# RK-POWER-SUPPLY.net
KiCad netlist of a schematic drawn in Altium Designer
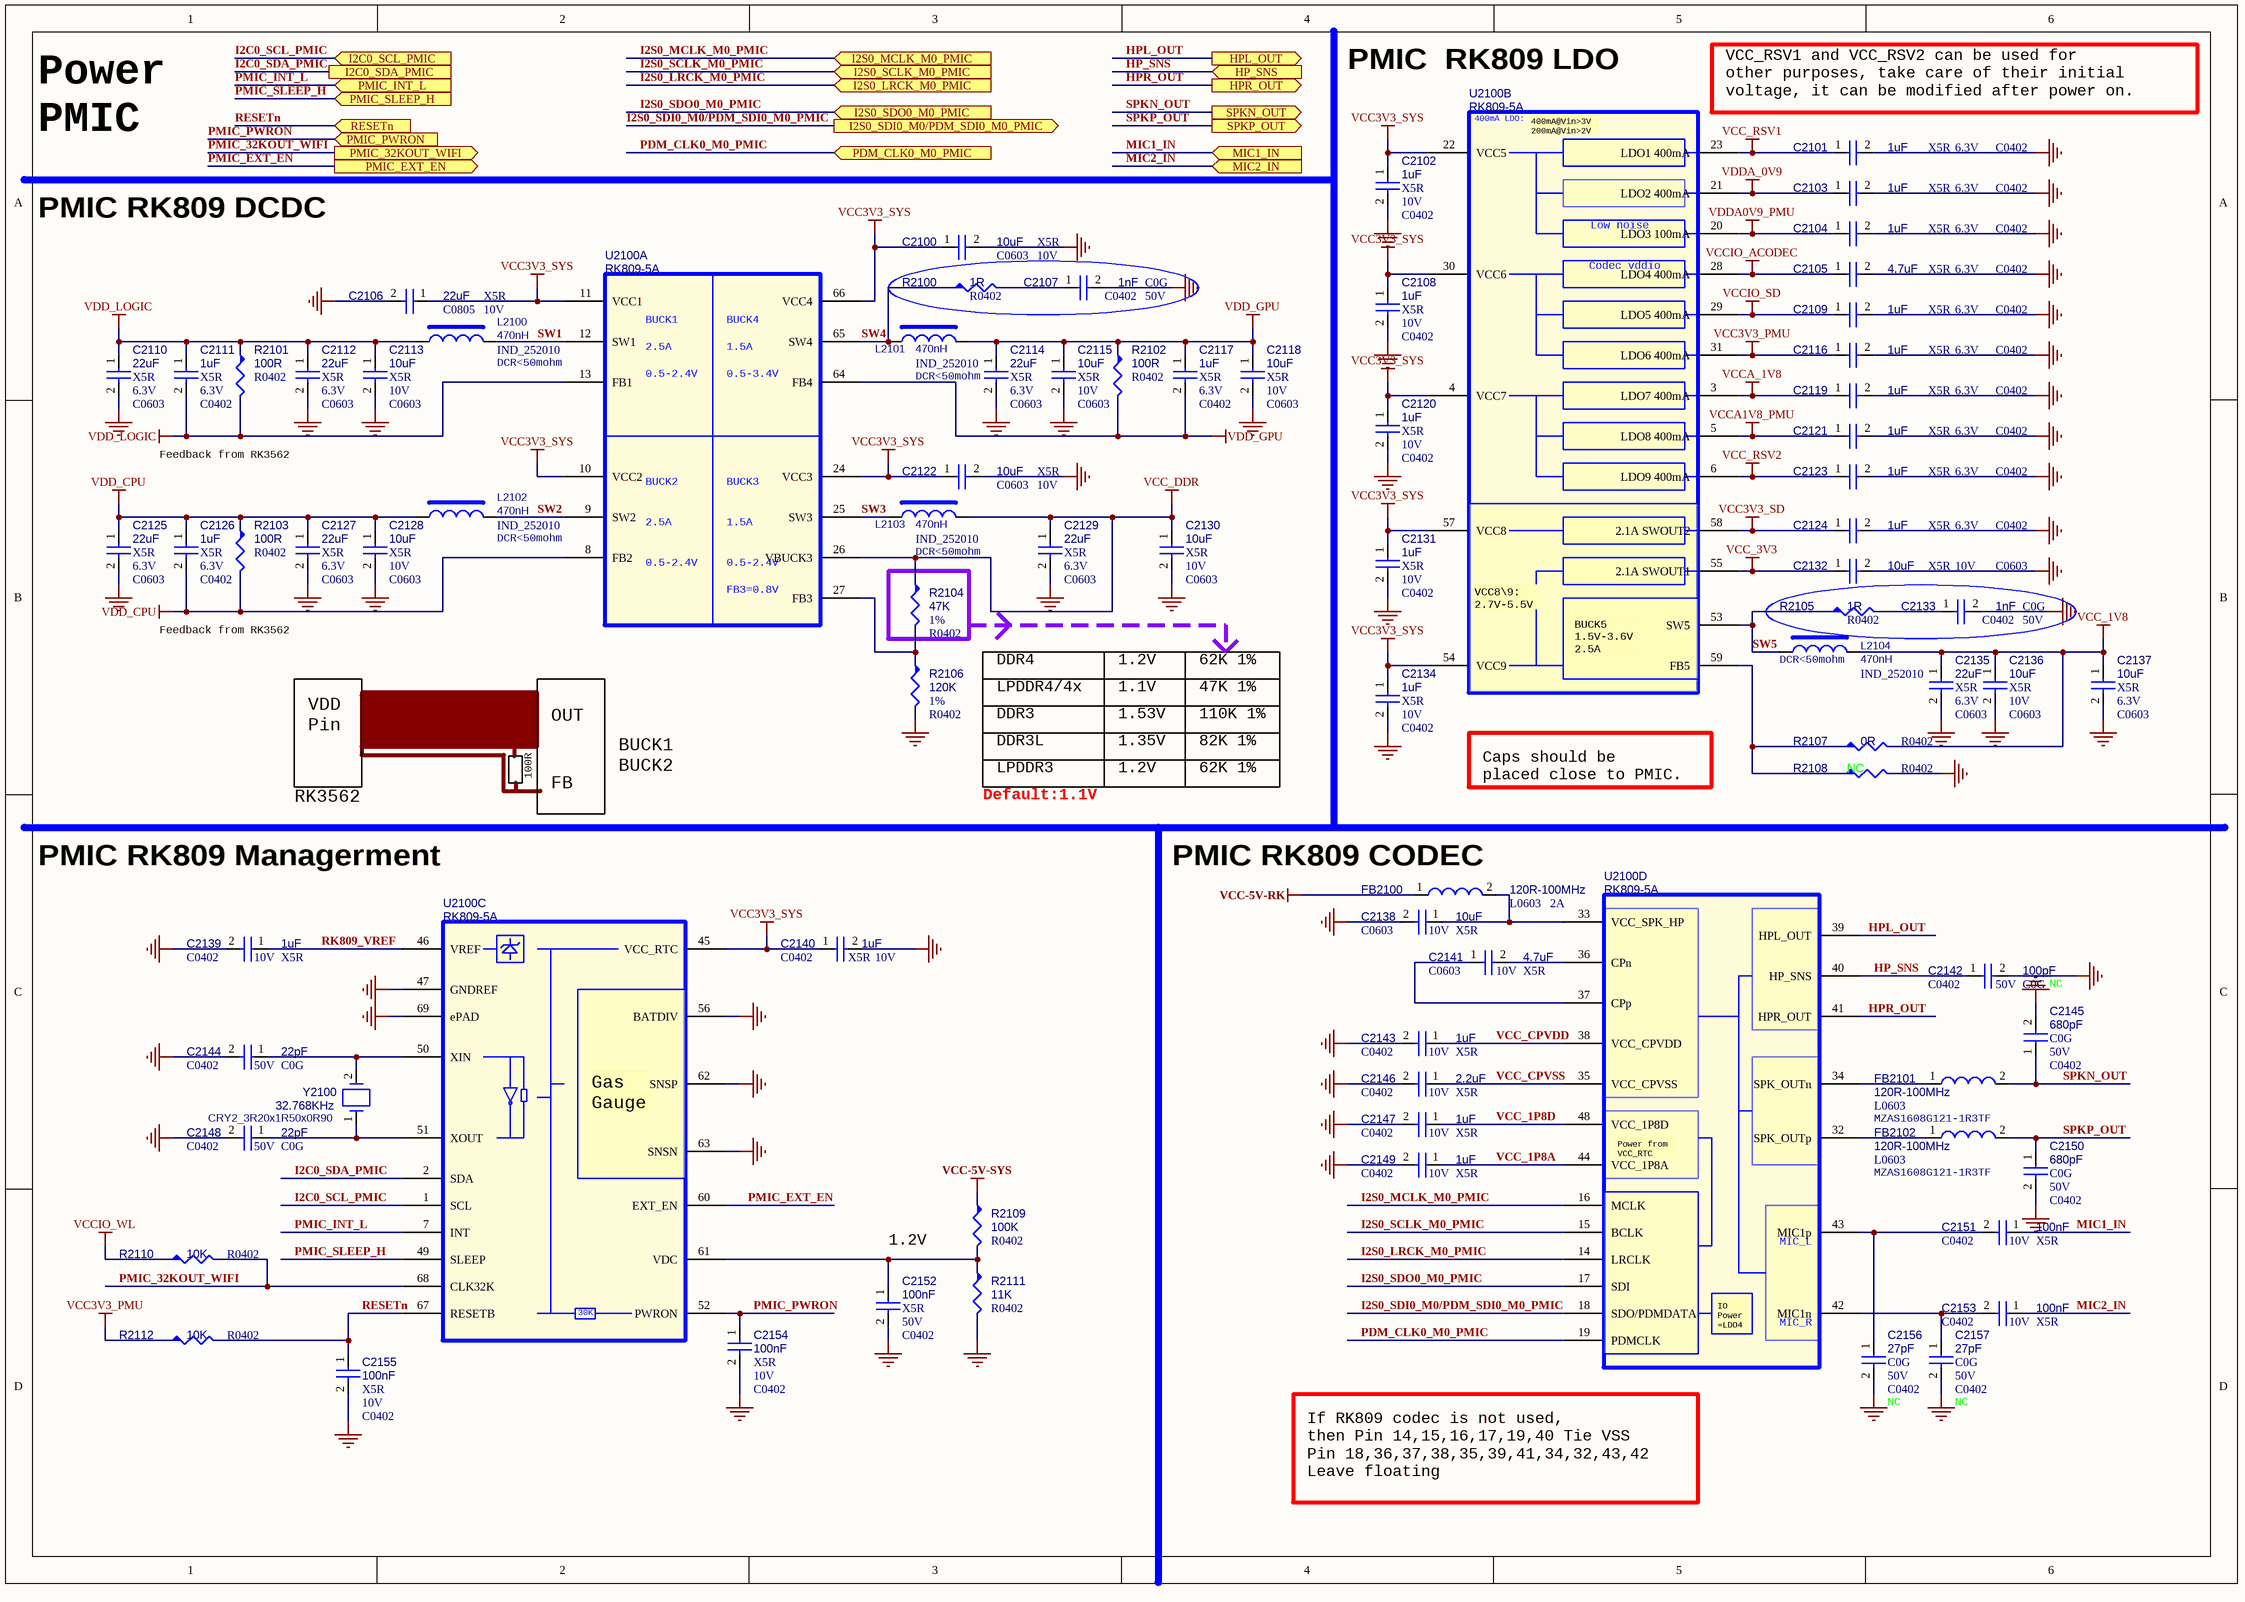
[diagram p0: RK-POWER-SUPPLY.SchDoc]

(export (version "E")
  (design (tool "Eeschema 10.0.6"))
  (components
    (comp (ref "C2100")
      (value "10uF")
      (footprint "C0603")
      (description "cap,10.00uF,+/-10%,10V,X5R,C0603")
      (fields
        (field (name "DIELECTRIC") "X5R")
        (field (name "PCB FOOTPRINT") "C0603")
        (field (name "VOLTAGE") "10V")
        (field (name "MANUFACTURER") "TDK")
        (field (name "TOLERANCE") "10%")
      )
      (libsource (lib "*") (part "CAP NP"))
    )
    (comp (ref "C2101")
      (value "1uF")
      (footprint "C0402")
      (description "cap,1.00uF,+/-10%,6.3V,X5R,C0402")
      (fields
        (field (name "DIELECTRIC") "X5R")
        (field (name "PCB FOOTPRINT") "C0402")
        (field (name "VOLTAGE") "6.3V")
        (field (name "TOLERANCE") "10%")
        (field (name "MANUFACTURER") "TDK")
      )
      (libsource (lib "*") (part "CAP NP"))
    )
    (comp (ref "C2102")
      (value "1uF")
      (footprint "C0402")
      (description "cap,1.00uF,+/-10%,10V,X5R,C0402")
      (fields
        (field (name "DIELECTRIC") "X5R")
        (field (name "PCB FOOTPRINT") "C0402")
        (field (name "VOLTAGE") "10V")
        (field (name "TOLERANCE") "10%")
        (field (name "MANUFACTURER") "TDK")
      )
      (libsource (lib "*") (part "CAP NP"))
    )
    (comp (ref "C2103")
      (value "1uF")
      (footprint "C0402")
      (description "cap,1.00uF,+/-10%,6.3V,X5R,C0402")
      (fields
        (field (name "DIELECTRIC") "X5R")
        (field (name "PCB FOOTPRINT") "C0402")
        (field (name "VOLTAGE") "6.3V")
        (field (name "TOLERANCE") "10%")
        (field (name "MANUFACTURER") "TDK")
      )
      (libsource (lib "*") (part "CAP NP"))
    )
    (comp (ref "C2104")
      (value "1uF")
      (footprint "C0402")
      (description "cap,1.00uF,+/-10%,6.3V,X5R,C0402")
      (fields
        (field (name "DIELECTRIC") "X5R")
        (field (name "PCB FOOTPRINT") "C0402")
        (field (name "VOLTAGE") "6.3V")
        (field (name "TOLERANCE") "10%")
        (field (name "MANUFACTURER") "TDK")
      )
      (libsource (lib "*") (part "CAP NP"))
    )
    (comp (ref "C2105")
      (value "4.7uF")
      (footprint "C0402")
      (description "cap,4.70uF,+/-10%,6.3V,X5R,C0402")
      (fields
        (field (name "DIELECTRIC") "X5R")
        (field (name "PCB FOOTPRINT") "C0402")
        (field (name "VOLTAGE") "6.3V")
        (field (name "MANUFACTURER") "TDK")
        (field (name "TOLERANCE") "10%")
      )
      (libsource (lib "*") (part "CAP NP"))
    )
    (comp (ref "C2106")
      (value "22uF")
      (footprint "CAP-0805-S")
      (description "cap,22.00uF,+/-10%,10V,X5R,C0805")
      (fields
        (field (name "DIELECTRIC") "X5R")
        (field (name "PCB FOOTPRINT") "C0805")
        (field (name "VOLTAGE") "10V")
        (field (name "MANUFACTURER") "TDK")
        (field (name "TOLERANCE") "10%")
      )
      (libsource (lib "*") (part "CAP NP"))
    )
    (comp (ref "C2107")
      (value "1nF")
      (footprint "C0402")
      (description "一般用片状陶瓷电容(GRM),cap,1nF,±5%,50V,C0G,C0402")
      (fields
        (field (name "DIELECTRIC") "C0G")
        (field (name "PCB FOOTPRINT") "C0402")
        (field (name "VOLTAGE") "50V")
        (field (name "TOLERANCE") "±5%")
        (field (name "MANUFACTURER") "murata")
      )
      (libsource (lib "*") (part "CAP NP"))
    )
    (comp (ref "C2108")
      (value "1uF")
      (footprint "C0402")
      (description "cap,1.00uF,+/-10%,10V,X5R,C0402")
      (fields
        (field (name "DIELECTRIC") "X5R")
        (field (name "PCB FOOTPRINT") "C0402")
        (field (name "VOLTAGE") "10V")
        (field (name "TOLERANCE") "10%")
        (field (name "MANUFACTURER") "TDK")
      )
      (libsource (lib "*") (part "CAP NP"))
    )
    (comp (ref "C2109")
      (value "1uF")
      (footprint "C0402")
      (description "cap,1.00uF,+/-10%,6.3V,X5R,C0402")
      (fields
        (field (name "DIELECTRIC") "X5R")
        (field (name "PCB FOOTPRINT") "C0402")
        (field (name "VOLTAGE") "6.3V")
        (field (name "TOLERANCE") "10%")
        (field (name "MANUFACTURER") "TDK")
      )
      (libsource (lib "*") (part "CAP NP"))
    )
    (comp (ref "C2110")
      (value "22uF")
      (footprint "C0603")
      (description "cap,22.00uF,+/-20%,6.3V,X5R,C0603")
      (fields
        (field (name "DIELECTRIC") "X5R")
        (field (name "PCB FOOTPRINT") "C0603")
        (field (name "VOLTAGE") "6.3V")
        (field (name "TOLERANCE") "20%")
        (field (name "MANUFACTURER") "TDK")
      )
      (libsource (lib "*") (part "CAP NP"))
    )
    (comp (ref "C2111")
      (value "1uF")
      (footprint "C0402")
      (description "cap,1.00uF,+/-10%,6.3V,X5R,C0402")
      (fields
        (field (name "DIELECTRIC") "X5R")
        (field (name "PCB FOOTPRINT") "C0402")
        (field (name "VOLTAGE") "6.3V")
        (field (name "MANUFACTURER") "TDK")
        (field (name "TOLERANCE") "10%")
      )
      (libsource (lib "*") (part "CAP NP"))
    )
    (comp (ref "C2112")
      (value "22uF")
      (footprint "C0603")
      (description "cap,22.00uF,+/-20%,6.3V,X5R,C0603")
      (fields
        (field (name "DIELECTRIC") "X5R")
        (field (name "PCB FOOTPRINT") "C0603")
        (field (name "VOLTAGE") "6.3V")
        (field (name "TOLERANCE") "20%")
        (field (name "MANUFACTURER") "TDK")
      )
      (libsource (lib "*") (part "CAP NP"))
    )
    (comp (ref "C2113")
      (value "10uF")
      (footprint "C0603")
      (description "cap,10.00uF,+/-10%,10V,X5R,C0603")
      (fields
        (field (name "DIELECTRIC") "X5R")
        (field (name "PCB FOOTPRINT") "C0603")
        (field (name "VOLTAGE") "10V")
        (field (name "TOLERANCE") "10%")
        (field (name "MANUFACTURER") "TDK")
      )
      (libsource (lib "*") (part "CAP NP"))
    )
    (comp (ref "C2114")
      (value "22uF")
      (footprint "C0603")
      (description "cap,22.00uF,+/-20%,6.3V,X5R,C0603")
      (fields
        (field (name "DIELECTRIC") "X5R")
        (field (name "PCB FOOTPRINT") "C0603")
        (field (name "VOLTAGE") "6.3V")
        (field (name "MANUFACTURER") "TDK")
        (field (name "TOLERANCE") "20%")
      )
      (libsource (lib "*") (part "CAP NP"))
    )
    (comp (ref "C2115")
      (value "10uF")
      (footprint "C0603")
      (description "cap,10.00uF,+/-10%,10V,X5R,C0603")
      (fields
        (field (name "DIELECTRIC") "X5R")
        (field (name "PCB FOOTPRINT") "C0603")
        (field (name "VOLTAGE") "10V")
        (field (name "MANUFACTURER") "TDK")
        (field (name "TOLERANCE") "10%")
      )
      (libsource (lib "*") (part "CAP NP"))
    )
    (comp (ref "C2116")
      (value "1uF")
      (footprint "C0402")
      (description "cap,1.00uF,+/-10%,6.3V,X5R,C0402")
      (fields
        (field (name "DIELECTRIC") "X5R")
        (field (name "PCB FOOTPRINT") "C0402")
        (field (name "VOLTAGE") "6.3V")
        (field (name "TOLERANCE") "10%")
        (field (name "MANUFACTURER") "TDK")
      )
      (libsource (lib "*") (part "CAP NP"))
    )
    (comp (ref "C2117")
      (value "1uF")
      (footprint "C0402")
      (description "cap,1.00uF,+/-10%,6.3V,X5R,C0402")
      (fields
        (field (name "DIELECTRIC") "X5R")
        (field (name "PCB FOOTPRINT") "C0402")
        (field (name "VOLTAGE") "6.3V")
        (field (name "MANUFACTURER") "TDK")
        (field (name "TOLERANCE") "10%")
      )
      (libsource (lib "*") (part "CAP NP"))
    )
    (comp (ref "C2118")
      (value "10uF")
      (footprint "C0603")
      (description "cap,10.00uF,+/-10%,10V,X5R,C0603")
      (fields
        (field (name "DIELECTRIC") "X5R")
        (field (name "PCB FOOTPRINT") "C0603")
        (field (name "VOLTAGE") "10V")
        (field (name "MANUFACTURER") "TDK")
        (field (name "TOLERANCE") "10%")
      )
      (libsource (lib "*") (part "CAP NP"))
    )
    (comp (ref "C2119")
      (value "1uF")
      (footprint "C0402")
      (description "cap,1.00uF,+/-10%,6.3V,X5R,C0402")
      (fields
        (field (name "DIELECTRIC") "X5R")
        (field (name "PCB FOOTPRINT") "C0402")
        (field (name "VOLTAGE") "6.3V")
        (field (name "TOLERANCE") "10%")
        (field (name "MANUFACTURER") "TDK")
      )
      (libsource (lib "*") (part "CAP NP"))
    )
    (comp (ref "C2120")
      (value "1uF")
      (footprint "C0402")
      (description "cap,1.00uF,+/-10%,10V,X5R,C0402")
      (fields
        (field (name "DIELECTRIC") "X5R")
        (field (name "PCB FOOTPRINT") "C0402")
        (field (name "VOLTAGE") "10V")
        (field (name "TOLERANCE") "10%")
        (field (name "MANUFACTURER") "TDK")
      )
      (libsource (lib "*") (part "CAP NP"))
    )
    (comp (ref "C2121")
      (value "1uF")
      (footprint "C0402")
      (description "cap,1.00uF,+/-10%,6.3V,X5R,C0402")
      (fields
        (field (name "DIELECTRIC") "X5R")
        (field (name "PCB FOOTPRINT") "C0402")
        (field (name "VOLTAGE") "6.3V")
        (field (name "TOLERANCE") "10%")
        (field (name "MANUFACTURER") "TDK")
      )
      (libsource (lib "*") (part "CAP NP"))
    )
    (comp (ref "C2122")
      (value "10uF")
      (footprint "C0603")
      (description "cap,10.00uF,+/-10%,10V,X5R,C0603")
      (fields
        (field (name "DIELECTRIC") "X5R")
        (field (name "PCB FOOTPRINT") "C0603")
        (field (name "VOLTAGE") "10V")
        (field (name "MANUFACTURER") "TDK")
        (field (name "TOLERANCE") "10%")
      )
      (libsource (lib "*") (part "CAP NP"))
    )
    (comp (ref "C2123")
      (value "1uF")
      (footprint "C0402")
      (description "cap,1.00uF,+/-10%,6.3V,X5R,C0402")
      (fields
        (field (name "DIELECTRIC") "X5R")
        (field (name "PCB FOOTPRINT") "C0402")
        (field (name "VOLTAGE") "6.3V")
        (field (name "TOLERANCE") "10%")
        (field (name "MANUFACTURER") "TDK")
      )
      (libsource (lib "*") (part "CAP NP"))
    )
    (comp (ref "C2124")
      (value "1uF")
      (footprint "C0402")
      (description "cap,1.00uF,+/-10%,6.3V,X5R,C0402")
      (fields
        (field (name "DIELECTRIC") "X5R")
        (field (name "PCB FOOTPRINT") "C0402")
        (field (name "VOLTAGE") "6.3V")
        (field (name "TOLERANCE") "10%")
        (field (name "MANUFACTURER") "TDK")
      )
      (libsource (lib "*") (part "CAP NP"))
    )
    (comp (ref "C2125")
      (value "22uF")
      (footprint "C0603")
      (description "cap,22.00uF,+/-20%,6.3V,X5R,C0603")
      (fields
        (field (name "DIELECTRIC") "X5R")
        (field (name "PCB FOOTPRINT") "C0603")
        (field (name "VOLTAGE") "6.3V")
        (field (name "TOLERANCE") "20%")
        (field (name "MANUFACTURER") "TDK")
      )
      (libsource (lib "*") (part "CAP NP"))
    )
    (comp (ref "C2126")
      (value "1uF")
      (footprint "C0402")
      (description "cap,1.00uF,+/-10%,6.3V,X5R,C0402")
      (fields
        (field (name "DIELECTRIC") "X5R")
        (field (name "PCB FOOTPRINT") "C0402")
        (field (name "VOLTAGE") "6.3V")
        (field (name "TOLERANCE") "10%")
        (field (name "MANUFACTURER") "TDK")
      )
      (libsource (lib "*") (part "CAP NP"))
    )
    (comp (ref "C2127")
      (value "22uF")
      (footprint "C0603")
      (description "cap,22.00uF,+/-20%,6.3V,X5R,C0603")
      (fields
        (field (name "DIELECTRIC") "X5R")
        (field (name "PCB FOOTPRINT") "C0603")
        (field (name "VOLTAGE") "6.3V")
        (field (name "TOLERANCE") "20%")
        (field (name "MANUFACTURER") "TDK")
      )
      (libsource (lib "*") (part "CAP NP"))
    )
    (comp (ref "C2128")
      (value "10uF")
      (footprint "C0603")
      (description "cap,10.00uF,+/-10%,10V,X5R,C0603")
      (fields
        (field (name "DIELECTRIC") "X5R")
        (field (name "PCB FOOTPRINT") "C0603")
        (field (name "VOLTAGE") "10V")
        (field (name "MANUFACTURER") "TDK")
        (field (name "TOLERANCE") "10%")
      )
      (libsource (lib "*") (part "CAP NP"))
    )
    (comp (ref "C2129")
      (value "22uF")
      (footprint "C0603")
      (description "cap,22.00uF,+/-20%,6.3V,X5R,C0603")
      (fields
        (field (name "DIELECTRIC") "X5R")
        (field (name "PCB FOOTPRINT") "C0603")
        (field (name "VOLTAGE") "6.3V")
        (field (name "TOLERANCE") "20%")
        (field (name "MANUFACTURER") "TDK")
      )
      (libsource (lib "*") (part "CAP NP"))
    )
    (comp (ref "C2130")
      (value "10uF")
      (footprint "C0603")
      (description "cap,10.00uF,+/-10%,10V,X5R,C0603")
      (fields
        (field (name "DIELECTRIC") "X5R")
        (field (name "PCB FOOTPRINT") "C0603")
        (field (name "VOLTAGE") "10V")
        (field (name "MANUFACTURER") "TDK")
        (field (name "TOLERANCE") "10%")
      )
      (libsource (lib "*") (part "CAP NP"))
    )
    (comp (ref "C2131")
      (value "1uF")
      (footprint "C0402")
      (description "cap,1.00uF,+/-10%,10V,X5R,C0402")
      (fields
        (field (name "DIELECTRIC") "X5R")
        (field (name "PCB FOOTPRINT") "C0402")
        (field (name "VOLTAGE") "10V")
        (field (name "TOLERANCE") "10%")
        (field (name "MANUFACTURER") "TDK")
      )
      (libsource (lib "*") (part "CAP NP"))
    )
    (comp (ref "C2132")
      (value "10uF")
      (footprint "C0603")
      (description "cap,10.00uF,+/-10%,10V,X5R,C0603")
      (fields
        (field (name "DIELECTRIC") "X5R")
        (field (name "PCB FOOTPRINT") "C0603")
        (field (name "VOLTAGE") "10V")
        (field (name "MANUFACTURER") "TDK")
        (field (name "TOLERANCE") "10%")
      )
      (libsource (lib "*") (part "CAP NP"))
    )
    (comp (ref "C2133")
      (value "1nF")
      (footprint "C0402")
      (description "一般用片状陶瓷电容(GRM),cap,1nF,±5%,50V,C0G,C0402")
      (fields
        (field (name "DIELECTRIC") "C0G")
        (field (name "PCB FOOTPRINT") "C0402")
        (field (name "VOLTAGE") "50V")
        (field (name "MANUFACTURER") "murata")
        (field (name "TOLERANCE") "±5%")
      )
      (libsource (lib "*") (part "CAP NP"))
    )
    (comp (ref "C2134")
      (value "1uF")
      (footprint "C0402")
      (description "cap,1.00uF,+/-10%,10V,X5R,C0402")
      (fields
        (field (name "DIELECTRIC") "X5R")
        (field (name "PCB FOOTPRINT") "C0402")
        (field (name "VOLTAGE") "10V")
        (field (name "TOLERANCE") "10%")
        (field (name "MANUFACTURER") "TDK")
      )
      (libsource (lib "*") (part "CAP NP"))
    )
    (comp (ref "C2135")
      (value "22uF")
      (footprint "C0603")
      (description "cap,22.00uF,+/-20%,6.3V,X5R,C0603")
      (fields
        (field (name "DIELECTRIC") "X5R")
        (field (name "PCB FOOTPRINT") "C0603")
        (field (name "VOLTAGE") "6.3V")
        (field (name "TOLERANCE") "20%")
        (field (name "MANUFACTURER") "TDK")
      )
      (libsource (lib "*") (part "CAP NP"))
    )
    (comp (ref "C2136")
      (value "10uF")
      (footprint "C0603")
      (description "cap,10.00uF,+/-10%,10V,X5R,C0603")
      (fields
        (field (name "DIELECTRIC") "X5R")
        (field (name "PCB FOOTPRINT") "C0603")
        (field (name "VOLTAGE") "10V")
        (field (name "TOLERANCE") "10%")
        (field (name "MANUFACTURER") "TDK")
      )
      (libsource (lib "*") (part "CAP NP"))
    )
    (comp (ref "C2137")
      (value "10uF")
      (footprint "C0603")
      (description "一般用片状陶瓷电容(GRM),cap,10uF,±10%,6.3V,X5R,C0603")
      (fields
        (field (name "DIELECTRIC") "X5R")
        (field (name "PCB FOOTPRINT") "C0603")
        (field (name "VOLTAGE") "6.3V")
        (field (name "TOLERANCE") "±10%")
        (field (name "MANUFACTURER") "murata")
      )
      (libsource (lib "*") (part "CAP NP"))
    )
    (comp (ref "C2138")
      (value "10uF")
      (footprint "C0603")
      (description "cap,10.00uF,+/-10%,10V,X5R,C0603")
      (fields
        (field (name "DIELECTRIC") "X5R")
        (field (name "PCB FOOTPRINT") "C0603")
        (field (name "VOLTAGE") "10V")
        (field (name "MANUFACTURER") "TDK")
        (field (name "TOLERANCE") "10%")
      )
      (libsource (lib "*") (part "CAP NP"))
    )
    (comp (ref "C2139")
      (value "1uF")
      (footprint "C0402")
      (description "cap,1.00uF,+/-10%,10V,X5R,C0402")
      (fields
        (field (name "DIELECTRIC") "X5R")
        (field (name "PCB FOOTPRINT") "C0402")
        (field (name "VOLTAGE") "10V")
        (field (name "MANUFACTURER") "TDK")
        (field (name "TOLERANCE") "10%")
      )
      (libsource (lib "*") (part "CAP NP"))
    )
    (comp (ref "C2140")
      (value "1uF")
      (footprint "C0402")
      (description "cap,1.00uF,+/-10%,10V,X5R,C0402")
      (fields
        (field (name "DIELECTRIC") "X5R")
        (field (name "PCB FOOTPRINT") "C0402")
        (field (name "VOLTAGE") "10V")
        (field (name "MANUFACTURER") "TDK")
        (field (name "TOLERANCE") "10%")
      )
      (libsource (lib "*") (part "CAP NP"))
    )
    (comp (ref "C2141")
      (value "4.7uF")
      (footprint "C0603")
      (description "cap,4.70uF,+/-10%,10V,X5R,C0603")
      (fields
        (field (name "DIELECTRIC") "X5R")
        (field (name "PCB FOOTPRINT") "C0603")
        (field (name "VOLTAGE") "10V")
        (field (name "TOLERANCE") "10%")
        (field (name "MANUFACTURER") "TDK")
      )
      (libsource (lib "*") (part "CAP NP"))
    )
    (comp (ref "C2142")
      (value "100pF")
      (footprint "C0402")
      (description "cap,100.00pF,+/-10%,50V,C0G,C0402")
      (fields
        (field (name "DIELECTRIC") "C0G")
        (field (name "PCB FOOTPRINT") "C0402")
        (field (name "VOLTAGE") "50V")
        (field (name "OPTION") "NC")
        (field (name "MANUFACTURER") "TDK")
        (field (name "TOLERANCE") "10%")
      )
      (libsource (lib "*") (part "CAP NP"))
    )
    (comp (ref "C2143")
      (value "1uF")
      (footprint "C0402")
      (description "cap,1.00uF,+/-10%,10V,X5R,C0402")
      (fields
        (field (name "DIELECTRIC") "X5R")
        (field (name "PCB FOOTPRINT") "C0402")
        (field (name "VOLTAGE") "10V")
        (field (name "MANUFACTURER") "TDK")
        (field (name "TOLERANCE") "10%")
      )
      (libsource (lib "*") (part "CAP NP"))
    )
    (comp (ref "C2144")
      (value "22pF")
      (footprint "C0402")
      (description "cap,22.00pF,+/-1%,50V,C0G,C0402")
      (fields
        (field (name "DIELECTRIC") "C0G")
        (field (name "PCB FOOTPRINT") "C0402")
        (field (name "VOLTAGE") "50V")
        (field (name "MANUFACTURER") "TDK")
        (field (name "TOLERANCE") "1%")
      )
      (libsource (lib "*") (part "CAP NP"))
    )
    (comp (ref "C2145")
      (value "680pF")
      (footprint "C0402")
      (description "cap,680.00pF,+/-5%,50V,C0G,C0402")
      (fields
        (field (name "DIELECTRIC") "C0G")
        (field (name "PCB FOOTPRINT") "C0402")
        (field (name "VOLTAGE") "50V")
        (field (name "MANUFACTURER") "TDK")
        (field (name "TOLERANCE") "5%")
      )
      (libsource (lib "*") (part "CAP NP"))
    )
    (comp (ref "C2146")
      (value "2.2uF")
      (footprint "C0402")
      (description "cap,2.20uF,+/-10%,10V,X5R,C0402")
      (fields
        (field (name "DIELECTRIC") "X5R")
        (field (name "PCB FOOTPRINT") "C0402")
        (field (name "VOLTAGE") "10V")
        (field (name "TOLERANCE") "10%")
        (field (name "MANUFACTURER") "TDK")
      )
      (libsource (lib "*") (part "CAP NP"))
    )
    (comp (ref "C2147")
      (value "1uF")
      (footprint "C0402")
      (description "cap,1.00uF,+/-10%,10V,X5R,C0402")
      (fields
        (field (name "DIELECTRIC") "X5R")
        (field (name "PCB FOOTPRINT") "C0402")
        (field (name "VOLTAGE") "10V")
        (field (name "MANUFACTURER") "TDK")
        (field (name "TOLERANCE") "10%")
      )
      (libsource (lib "*") (part "CAP NP"))
    )
    (comp (ref "C2148")
      (value "22pF")
      (footprint "C0402")
      (description "cap,22.00pF,+/-1%,50V,C0G,C0402")
      (fields
        (field (name "DIELECTRIC") "C0G")
        (field (name "PCB FOOTPRINT") "C0402")
        (field (name "VOLTAGE") "50V")
        (field (name "MANUFACTURER") "TDK")
        (field (name "TOLERANCE") "1%")
      )
      (libsource (lib "*") (part "CAP NP"))
    )
    (comp (ref "C2149")
      (value "1uF")
      (footprint "C0402")
      (description "cap,1.00uF,+/-10%,10V,X5R,C0402")
      (fields
        (field (name "DIELECTRIC") "X5R")
        (field (name "PCB FOOTPRINT") "C0402")
        (field (name "VOLTAGE") "10V")
        (field (name "TOLERANCE") "10%")
        (field (name "MANUFACTURER") "TDK")
      )
      (libsource (lib "*") (part "CAP NP"))
    )
    (comp (ref "C2150")
      (value "680pF")
      (footprint "C0402")
      (description "cap,680.00pF,+/-5%,50V,C0G,C0402")
      (fields
        (field (name "DIELECTRIC") "C0G")
        (field (name "PCB FOOTPRINT") "C0402")
        (field (name "VOLTAGE") "50V")
        (field (name "MANUFACTURER") "TDK")
        (field (name "TOLERANCE") "5%")
      )
      (libsource (lib "*") (part "CAP NP"))
    )
    (comp (ref "C2151")
      (value "100nF")
      (footprint "C0402")
      (description "cap,100.00nF,+/-10%,10V,X5R,C0402")
      (fields
        (field (name "DIELECTRIC") "X5R")
        (field (name "PCB FOOTPRINT") "C0402")
        (field (name "VOLTAGE") "10V")
        (field (name "TOLERANCE") "10%")
        (field (name "MANUFACTURER") "TDK")
      )
      (libsource (lib "*") (part "CAP NP"))
    )
    (comp (ref "C2152")
      (value "100nF")
      (footprint "C0402")
      (description "一般用片状陶瓷电容(GRM),cap,100nF,±10%,50V,X5R,C0402")
      (fields
        (field (name "DIELECTRIC") "X5R")
        (field (name "PCB FOOTPRINT") "C0402")
        (field (name "VOLTAGE") "50V")
        (field (name "MANUFACTURER") "murata")
        (field (name "TOLERANCE") "±10%")
      )
      (libsource (lib "*") (part "CAP NP"))
    )
    (comp (ref "C2153")
      (value "100nF")
      (footprint "C0402")
      (description "cap,100.00nF,+/-10%,10V,X5R,C0402")
      (fields
        (field (name "DIELECTRIC") "X5R")
        (field (name "PCB FOOTPRINT") "C0402")
        (field (name "VOLTAGE") "10V")
        (field (name "MANUFACTURER") "TDK")
        (field (name "TOLERANCE") "10%")
      )
      (libsource (lib "*") (part "CAP NP"))
    )
    (comp (ref "C2154")
      (value "100nF")
      (footprint "C0402")
      (description "cap,100.00nF,+/-10%,10V,X5R,C0402")
      (fields
        (field (name "DIELECTRIC") "X5R")
        (field (name "PCB FOOTPRINT") "C0402")
        (field (name "VOLTAGE") "10V")
        (field (name "MANUFACTURER") "TDK")
        (field (name "TOLERANCE") "10%")
      )
      (libsource (lib "*") (part "CAP NP"))
    )
    (comp (ref "C2155")
      (value "100nF")
      (footprint "C0402")
      (description "cap,100.00nF,+/-10%,10V,X5R,C0402")
      (fields
        (field (name "DIELECTRIC") "X5R")
        (field (name "PCB FOOTPRINT") "C0402")
        (field (name "VOLTAGE") "10V")
        (field (name "MANUFACTURER") "TDK")
        (field (name "TOLERANCE") "10%")
      )
      (libsource (lib "*") (part "CAP NP"))
    )
    (comp (ref "C2156")
      (value "27pF")
      (footprint "C0402")
      (description "cap,27.00pF,+/-5%,50V,C0G,C0402")
      (fields
        (field (name "DIELECTRIC") "C0G")
        (field (name "PCB FOOTPRINT") "C0402")
        (field (name "VOLTAGE") "50V")
        (field (name "OPTION") "NC")
        (field (name "TOLERANCE") "5%")
        (field (name "MANUFACTURER") "TDK")
      )
      (libsource (lib "*") (part "CAP NP"))
    )
    (comp (ref "C2157")
      (value "27pF")
      (footprint "C0402")
      (description "cap,27.00pF,+/-5%,50V,C0G,C0402")
      (fields
        (field (name "DIELECTRIC") "C0G")
        (field (name "PCB FOOTPRINT") "C0402")
        (field (name "VOLTAGE") "50V")
        (field (name "MANUFACTURER") "TDK")
        (field (name "TOLERANCE") "5%")
        (field (name "OPTION") "NC")
      )
      (libsource (lib "*") (part "CAP NP"))
    )
    (comp (ref "FB2100")
      (value "120R-100MHz")
      (footprint "L0603")
      (description "BEAD,120R@100MHz,current=2000mA,0603")
      (fields
        (field (name "TOLERANCE") "25%")
        (field (name "PCB FOOTPRINT") "L0603")
        (field (name "IRMS") "2A")
        (field (name "MANUFACTURER") "Murata")
      )
      (libsource (lib "*") (part "BEAD"))
    )
    (comp (ref "FB2101")
      (value "120R-100MHz")
      (footprint "L0603")
      (description "BEAD,120R@100MHz,current=2000mA,0603")
      (fields
        (field (name "TOLERANCE") "25%")
        (field (name "PCB FOOTPRINT") "L0603")
        (field (name "MANUFACTURER") "SUNLORD")
        (field (name "MANUFACTURER PN") "MZAS1608G121-1R3TF")
      )
      (libsource (lib "*") (part "BEAD"))
    )
    (comp (ref "FB2102")
      (value "120R-100MHz")
      (footprint "L0603")
      (description "BEAD,120R@100MHz,current=2000mA,0603")
      (fields
        (field (name "TOLERANCE") "25%")
        (field (name "PCB FOOTPRINT") "L0603")
        (field (name "MANUFACTURER PN") "MZAS1608G121-1R3TF")
        (field (name "MANUFACTURER") "SUNLORD")
      )
      (libsource (lib "*") (part "BEAD"))
    )
    (comp (ref "L2100")
      (value "470nH")
      (footprint "IND_252010")
      (description "Power Inductor,470nH,0.2,IND_252010")
      (fields
        (field (name "PCB FOOTPRINT") "IND_252010")
        (field (name "MANUFACTURER") "TDK")
        (field (name "TOLERANCE") "20%")
        (field (name "OPTION") "DCR<50mohm")
      )
      (libsource (lib "*") (part "INDUCTORS OF FERRITE"))
    )
    (comp (ref "L2101")
      (value "470nH")
      (footprint "IND_252010")
      (description "Power Inductor,470nH,0.2,IND_252010")
      (fields
        (field (name "PCB FOOTPRINT") "IND_252010")
        (field (name "MANUFACTURER") "TDK")
        (field (name "TOLERANCE") "20%")
        (field (name "OPTION") "DCR<50mohm")
      )
      (libsource (lib "*") (part "INDUCTORS OF FERRITE"))
    )
    (comp (ref "L2102")
      (value "470nH")
      (footprint "IND_252010")
      (description "Power Inductor,470nH,0.2,IND_252010")
      (fields
        (field (name "PCB FOOTPRINT") "IND_252010")
        (field (name "MANUFACTURER") "TDK")
        (field (name "TOLERANCE") "20%")
        (field (name "OPTION") "DCR<50mohm")
      )
      (libsource (lib "*") (part "INDUCTORS OF FERRITE"))
    )
    (comp (ref "L2103")
      (value "470nH")
      (footprint "IND_252010")
      (description "Power Inductor,470nH,0.2,IND_252010")
      (fields
        (field (name "PCB FOOTPRINT") "IND_252010")
        (field (name "MANUFACTURER") "TDK")
        (field (name "TOLERANCE") "20%")
        (field (name "OPTION") "DCR<50mohm")
      )
      (libsource (lib "*") (part "INDUCTORS OF FERRITE"))
    )
    (comp (ref "L2104")
      (value "470nH")
      (footprint "IND_252010")
      (description "Power Inductor,470nH,0.2,IND_252010")
      (fields
        (field (name "PCB FOOTPRINT") "IND_252010")
        (field (name "TOLERANCE") "20%")
        (field (name "MANUFACTURER") "TDK")
        (field (name "OPTION") "DCR<50mohm")
      )
      (libsource (lib "*") (part "INDUCTORS OF FERRITE"))
    )
    (comp (ref "R2100")
      (value "1R")
      (footprint "R0402")
      (description "通用厚膜电阻,1R,+/-5%,R0402,1/16W.")
      (fields
        (field (name "TOLERANCE") "5%")
        (field (name "PCB FOOTPRINT") "R0402")
        (field (name "MANUFACTURER") "YAGEO")
      )
      (libsource (lib "*") (part "RESISTOR5"))
    )
    (comp (ref "R2101")
      (value "100R")
      (footprint "R0402")
      (description "通用厚膜电阻,100R,+/-5%,R0402,1/16W.")
      (fields
        (field (name "TOLERANCE") "5%")
        (field (name "PCB FOOTPRINT") "R0402")
        (field (name "MANUFACTURER") "YAGEO")
      )
      (libsource (lib "*") (part "RESISTOR5"))
    )
    (comp (ref "R2102")
      (value "100R")
      (footprint "R0402")
      (description "通用厚膜电阻,100R,+/-5%,R0402,1/16W.")
      (fields
        (field (name "TOLERANCE") "5%")
        (field (name "PCB FOOTPRINT") "R0402")
        (field (name "MANUFACTURER") "YAGEO")
      )
      (libsource (lib "*") (part "RESISTOR5"))
    )
    (comp (ref "R2103")
      (value "100R")
      (footprint "R0402")
      (description "通用厚膜电阻,100R,+/-5%,R0402,1/16W.")
      (fields
        (field (name "TOLERANCE") "5%")
        (field (name "PCB FOOTPRINT") "R0402")
        (field (name "MANUFACTURER") "YAGEO")
      )
      (libsource (lib "*") (part "RESISTOR5"))
    )
    (comp (ref "R2104")
      (value "47K")
      (footprint "R0402")
      (description "通用厚膜电阻,47K,+/-1%,R0402,1/16W.")
      (fields
        (field (name "TOLERANCE") "1%")
        (field (name "PCB FOOTPRINT") "R0402")
        (field (name "MANUFACTURER") "YAGEO")
      )
      (libsource (lib "*") (part "RESISTOR1"))
    )
    (comp (ref "R2105")
      (value "1R")
      (footprint "R0402")
      (description "通用厚膜电阻,1R,+/-5%,R0402,1/16W.")
      (fields
        (field (name "TOLERANCE") "5%")
        (field (name "PCB FOOTPRINT") "R0402")
        (field (name "MANUFACTURER") "YAGEO")
      )
      (libsource (lib "*") (part "RESISTOR5"))
    )
    (comp (ref "R2106")
      (value "120K")
      (footprint "R0402")
      (description "通用厚膜电阻,120K,+/-1%,R0402,1/16W.")
      (fields
        (field (name "TOLERANCE") "1%")
        (field (name "PCB FOOTPRINT") "R0402")
        (field (name "MANUFACTURER") "YAGEO")
      )
      (libsource (lib "*") (part "RESISTOR1"))
    )
    (comp (ref "R2107")
      (value "0R")
      (footprint "R0402")
      (description "通用厚膜电阻,0R,+/-5%,R0402,1/16W.")
      (fields
        (field (name "TOLERANCE") "5%")
        (field (name "PCB FOOTPRINT") "R0402")
        (field (name "MANUFACTURER") "YAGEO")
      )
      (libsource (lib "*") (part "RESISTOR5"))
    )
    (comp (ref "R2108")
      (value "NC")
      (footprint "R0402")
      (description "NC电阻，无阻值.")
      (fields (field (name "PCB FOOTPRINT") "R0402"))
      (libsource (lib "*") (part "RESISTOR5_NC"))
    )
    (comp (ref "R2109")
      (value "100K")
      (footprint "R0402")
      (description "通用厚膜电阻,100K,+/-5%,R0402,1/16W.")
      (fields
        (field (name "TOLERANCE") "5%")
        (field (name "PCB FOOTPRINT") "R0402")
        (field (name "MANUFACTURER") "YAGEO")
      )
      (libsource (lib "*") (part "RESISTOR5"))
    )
    (comp (ref "R2110")
      (value "10K")
      (footprint "R0402")
      (description "通用厚膜电阻,10K,+/-5%,R0402,1/16W.")
      (fields
        (field (name "TOLERANCE") "5%")
        (field (name "PCB FOOTPRINT") "R0402")
        (field (name "MANUFACTURER") "YAGEO")
      )
      (libsource (lib "*") (part "RESISTOR5"))
    )
    (comp (ref "R2111")
      (value "11K")
      (footprint "R0402")
      (description "通用厚膜电阻,11K,+/-5%,R0402,1/16W.")
      (fields
        (field (name "TOLERANCE") "5%")
        (field (name "PCB FOOTPRINT") "R0402")
        (field (name "MANUFACTURER") "YAGEO")
      )
      (libsource (lib "*") (part "RESISTOR5"))
    )
    (comp (ref "R2112")
      (value "10K")
      (footprint "R0402")
      (description "通用厚膜电阻,10K,+/-5%,R0402,1/16W.")
      (fields
        (field (name "TOLERANCE") "5%")
        (field (name "PCB FOOTPRINT") "R0402")
        (field (name "MANUFACTURER") "YAGEO")
      )
      (libsource (lib "*") (part "RESISTOR5"))
    )
    (comp (ref "U2100")
      (value "RK809-5A")
      (footprint "QFN-68_L7.0-W7.0-P0.35-BL-EP5.5")
      (description "ROCKCHIP PMIC RK809-5A")
      (fields (field (name "MANUFACTURER") "Rockchip (瑞芯微)"))
      (libsource (lib "*") (part "PMIC_RK809"))
    )
    (comp (ref "Y2100")
      (value "32.768KHz")
      (footprint "CRY2_3R20x1R50x0R90")
      (description "无源晶振，32.768KHz,±20ppm，12.5pF")
      (fields (field (name "PCB FOOTPRINT") "CRY2_3R20x1R50x0R90") (field (name "MANUFACTURER") "TKD(泰晶)"))
      (libsource (lib "*") (part "CRYSTAL_2P"))
    )
  )
  (nets
    (net (code "1") (name "/HPL_OUT") (class "Default")
      (node (ref "U2100") (pin "39") (pinfunction "HPL_OUT_39") (pintype "passive"))
    )
    (net (code "2") (name "/HPR_OUT") (class "Default")
      (node (ref "U2100") (pin "41") (pinfunction "HPR_OUT_41") (pintype "passive"))
    )
    (net (code "3") (name "/HP_SNS") (class "Default")
      (node (ref "C2142") (pin "1") (pinfunction "1_1") (pintype "passive"))
      (node (ref "U2100") (pin "40") (pinfunction "HP_SNS_40") (pintype "passive"))
    )
    (net (code "4") (name "/I2C0_SCL_PMIC") (class "Default")
      (node (ref "U2100") (pin "1") (pinfunction "SCL_1") (pintype "passive"))
    )
    (net (code "5") (name "/I2C0_SDA_PMIC") (class "Default")
      (node (ref "U2100") (pin "2") (pinfunction "SDA_2") (pintype "passive"))
    )
    (net (code "6") (name "/I2S0_LRCK_M0_PMIC") (class "Default")
      (node (ref "U2100") (pin "14") (pinfunction "LRCLK_14") (pintype "passive"))
    )
    (net (code "7") (name "/I2S0_MCLK_M0_PMIC") (class "Default")
      (node (ref "U2100") (pin "16") (pinfunction "MCLK_16") (pintype "passive"))
    )
    (net (code "8") (name "/I2S0_SCLK_M0_PMIC") (class "Default")
      (node (ref "U2100") (pin "15") (pinfunction "BCLK_15") (pintype "passive"))
    )
    (net (code "9") (name "/I2S0_SDI0_M0{slash}PDM_SDI0_M0_PMIC") (class "Default")
      (node (ref "U2100") (pin "18") (pinfunction "SDO/PDMDATA_18") (pintype "passive"))
    )
    (net (code "10") (name "/I2S0_SDO0_M0_PMIC") (class "Default")
      (node (ref "U2100") (pin "17") (pinfunction "SDI_17") (pintype "passive"))
    )
    (net (code "11") (name "/MIC1_IN") (class "Default")
      (node (ref "C2151") (pin "1") (pinfunction "1_1") (pintype "passive"))
    )
    (net (code "12") (name "/MIC2_IN") (class "Default")
      (node (ref "C2153") (pin "1") (pinfunction "1_1") (pintype "passive"))
    )
    (net (code "13") (name "/PDM_CLK0_M0_PMIC") (class "Default")
      (node (ref "U2100") (pin "19") (pinfunction "PDMCLK_19") (pintype "passive"))
    )
    (net (code "14") (name "/PMIC_32KOUT_WIFI") (class "Default")
      (node (ref "R2110") (pin "2") (pinfunction "2_2") (pintype "passive"))
      (node (ref "U2100") (pin "68") (pinfunction "CLK32K_68") (pintype "passive"))
    )
    (net (code "15") (name "/PMIC_EXT_EN") (class "Default")
      (node (ref "U2100") (pin "60") (pinfunction "EXT_EN_60") (pintype "passive"))
    )
    (net (code "16") (name "/PMIC_INT_L") (class "Default")
      (node (ref "U2100") (pin "7") (pinfunction "INT_7") (pintype "passive"))
    )
    (net (code "17") (name "/PMIC_PWRON") (class "Default")
      (node (ref "C2154") (pin "1") (pinfunction "1_1") (pintype "passive"))
      (node (ref "U2100") (pin "52") (pinfunction "PWRON_52") (pintype "passive"))
    )
    (net (code "18") (name "/PMIC_SLEEP_H") (class "Default")
      (node (ref "U2100") (pin "49") (pinfunction "SLEEP_49") (pintype "passive"))
    )
    (net (code "19") (name "/RESETn") (class "Default")
      (node (ref "C2155") (pin "1") (pinfunction "1_1") (pintype "passive"))
      (node (ref "R2112") (pin "2") (pinfunction "2_2") (pintype "passive"))
      (node (ref "U2100") (pin "67") (pinfunction "RESETB_67") (pintype "passive"))
    )
    (net (code "20") (name "/RK809_VREF") (class "Default")
      (node (ref "C2139") (pin "1") (pinfunction "1_1") (pintype "passive"))
      (node (ref "U2100") (pin "46") (pinfunction "VREF_46") (pintype "passive"))
    )
    (net (code "21") (name "/SPKN_OUT") (class "Default")
      (node (ref "C2145") (pin "1") (pinfunction "1_1") (pintype "passive"))
      (node (ref "FB2101") (pin "2") (pinfunction "2_2") (pintype "passive"))
    )
    (net (code "22") (name "/SPKP_OUT") (class "Default")
      (node (ref "C2150") (pin "1") (pinfunction "1_1") (pintype "passive"))
      (node (ref "FB2102") (pin "2") (pinfunction "2_2") (pintype "passive"))
    )
    (net (code "23") (name "/SW1") (class "Default")
      (node (ref "L2100") (pin "1") (pinfunction "1_1") (pintype "passive"))
      (node (ref "U2100") (pin "12") (pinfunction "SW1_12") (pintype "passive"))
    )
    (net (code "24") (name "/SW2") (class "Default")
      (node (ref "L2102") (pin "1") (pinfunction "1_1") (pintype "passive"))
      (node (ref "U2100") (pin "9") (pinfunction "SW2_9") (pintype "passive"))
    )
    (net (code "25") (name "/SW3") (class "Default")
      (node (ref "L2103") (pin "2") (pinfunction "2_2") (pintype "passive"))
      (node (ref "U2100") (pin "25") (pinfunction "SW3_25") (pintype "passive"))
    )
    (net (code "26") (name "/SW4") (class "Default")
      (node (ref "L2101") (pin "2") (pinfunction "2_2") (pintype "passive"))
      (node (ref "R2100") (pin "1") (pinfunction "1_1") (pintype "passive"))
      (node (ref "U2100") (pin "65") (pinfunction "SW4_65") (pintype "passive"))
    )
    (net (code "27") (name "/SW5") (class "Default")
      (node (ref "L2104") (pin "2") (pinfunction "2_2") (pintype "passive"))
      (node (ref "R2105") (pin "1") (pinfunction "1_1") (pintype "passive"))
      (node (ref "U2100") (pin "53") (pinfunction "SW5_53") (pintype "passive"))
    )
    (net (code "28") (name "/VCC_1P8A") (class "Default")
      (node (ref "C2149") (pin "1") (pinfunction "1_1") (pintype "passive"))
      (node (ref "U2100") (pin "44") (pinfunction "VCC_1P8A_44") (pintype "passive"))
    )
    (net (code "29") (name "/VCC_1P8D") (class "Default")
      (node (ref "C2147") (pin "1") (pinfunction "1_1") (pintype "passive"))
      (node (ref "U2100") (pin "48") (pinfunction "VCC_1P8D_48") (pintype "passive"))
    )
    (net (code "30") (name "/VCC_CPVDD") (class "Default")
      (node (ref "C2143") (pin "1") (pinfunction "1_1") (pintype "passive"))
      (node (ref "U2100") (pin "38") (pinfunction "VCC_CPVDD_38") (pintype "passive"))
    )
    (net (code "31") (name "/VCC_CPVSS") (class "Default")
      (node (ref "C2146") (pin "1") (pinfunction "1_1") (pintype "passive"))
      (node (ref "U2100") (pin "35") (pinfunction "VCC_CPVSS_35") (pintype "passive"))
    )
    (net (code "32") (name "GND") (class "Default")
      (node (ref "C2100") (pin "2") (pinfunction "2_2") (pintype "passive"))
      (node (ref "C2101") (pin "2") (pinfunction "2_2") (pintype "passive"))
      (node (ref "C2102") (pin "2") (pinfunction "2_2") (pintype "passive"))
      (node (ref "C2103") (pin "2") (pinfunction "2_2") (pintype "passive"))
      (node (ref "C2104") (pin "2") (pinfunction "2_2") (pintype "passive"))
      (node (ref "C2105") (pin "2") (pinfunction "2_2") (pintype "passive"))
      (node (ref "C2106") (pin "2") (pinfunction "2_2") (pintype "passive"))
      (node (ref "C2107") (pin "2") (pinfunction "2_2") (pintype "passive"))
      (node (ref "C2108") (pin "2") (pinfunction "2_2") (pintype "passive"))
      (node (ref "C2109") (pin "2") (pinfunction "2_2") (pintype "passive"))
      (node (ref "C2110") (pin "2") (pinfunction "2_2") (pintype "passive"))
      (node (ref "C2112") (pin "2") (pinfunction "2_2") (pintype "passive"))
      (node (ref "C2113") (pin "2") (pinfunction "2_2") (pintype "passive"))
      (node (ref "C2114") (pin "2") (pinfunction "2_2") (pintype "passive"))
      (node (ref "C2115") (pin "2") (pinfunction "2_2") (pintype "passive"))
      (node (ref "C2116") (pin "2") (pinfunction "2_2") (pintype "passive"))
      (node (ref "C2118") (pin "2") (pinfunction "2_2") (pintype "passive"))
      (node (ref "C2119") (pin "2") (pinfunction "2_2") (pintype "passive"))
      (node (ref "C2120") (pin "2") (pinfunction "2_2") (pintype "passive"))
      (node (ref "C2121") (pin "2") (pinfunction "2_2") (pintype "passive"))
      (node (ref "C2122") (pin "2") (pinfunction "2_2") (pintype "passive"))
      (node (ref "C2123") (pin "2") (pinfunction "2_2") (pintype "passive"))
      (node (ref "C2124") (pin "2") (pinfunction "2_2") (pintype "passive"))
      (node (ref "C2125") (pin "2") (pinfunction "2_2") (pintype "passive"))
      (node (ref "C2127") (pin "2") (pinfunction "2_2") (pintype "passive"))
      (node (ref "C2128") (pin "2") (pinfunction "2_2") (pintype "passive"))
      (node (ref "C2129") (pin "2") (pinfunction "2_2") (pintype "passive"))
      (node (ref "C2130") (pin "2") (pinfunction "2_2") (pintype "passive"))
      (node (ref "C2131") (pin "2") (pinfunction "2_2") (pintype "passive"))
      (node (ref "C2132") (pin "2") (pinfunction "2_2") (pintype "passive"))
      (node (ref "C2133") (pin "2") (pinfunction "2_2") (pintype "passive"))
      (node (ref "C2134") (pin "2") (pinfunction "2_2") (pintype "passive"))
      (node (ref "C2135") (pin "2") (pinfunction "2_2") (pintype "passive"))
      (node (ref "C2136") (pin "2") (pinfunction "2_2") (pintype "passive"))
      (node (ref "C2137") (pin "2") (pinfunction "2_2") (pintype "passive"))
      (node (ref "C2138") (pin "2") (pinfunction "2_2") (pintype "passive"))
      (node (ref "C2139") (pin "2") (pinfunction "2_2") (pintype "passive"))
      (node (ref "C2140") (pin "2") (pinfunction "2_2") (pintype "passive"))
      (node (ref "C2142") (pin "2") (pinfunction "2_2") (pintype "passive"))
      (node (ref "C2143") (pin "2") (pinfunction "2_2") (pintype "passive"))
      (node (ref "C2144") (pin "2") (pinfunction "2_2") (pintype "passive"))
      (node (ref "C2145") (pin "2") (pinfunction "2_2") (pintype "passive"))
      (node (ref "C2146") (pin "2") (pinfunction "2_2") (pintype "passive"))
      (node (ref "C2147") (pin "2") (pinfunction "2_2") (pintype "passive"))
      (node (ref "C2148") (pin "2") (pinfunction "2_2") (pintype "passive"))
      (node (ref "C2149") (pin "2") (pinfunction "2_2") (pintype "passive"))
      (node (ref "C2150") (pin "2") (pinfunction "2_2") (pintype "passive"))
      (node (ref "C2152") (pin "2") (pinfunction "2_2") (pintype "passive"))
      (node (ref "C2154") (pin "2") (pinfunction "2_2") (pintype "passive"))
      (node (ref "C2155") (pin "2") (pinfunction "2_2") (pintype "passive"))
      (node (ref "C2156") (pin "2") (pinfunction "2_2") (pintype "passive"))
      (node (ref "C2157") (pin "2") (pinfunction "2_2") (pintype "passive"))
      (node (ref "R2106") (pin "2") (pinfunction "2_2") (pintype "passive"))
      (node (ref "R2108") (pin "2") (pinfunction "2_2") (pintype "passive"))
      (node (ref "R2111") (pin "2") (pinfunction "2_2") (pintype "passive"))
      (node (ref "U2100") (pin "47") (pinfunction "GNDREF_47") (pintype "passive"))
      (node (ref "U2100") (pin "56") (pinfunction "BATDIV_56") (pintype "passive"))
      (node (ref "U2100") (pin "62") (pinfunction "SNSP_62") (pintype "passive"))
      (node (ref "U2100") (pin "63") (pinfunction "SNSN_63") (pintype "passive"))
      (node (ref "U2100") (pin "69") (pinfunction "ePAD_69") (pintype "passive"))
    )
    (net (code "33") (name "Net-(C2107-Pad1)") (class "Default")
      (node (ref "C2107") (pin "1") (pinfunction "1_1") (pintype "passive"))
      (node (ref "R2100") (pin "2") (pinfunction "2_2") (pintype "passive"))
    )
    (net (code "34") (name "Net-(C2133-Pad1)") (class "Default")
      (node (ref "C2133") (pin "1") (pinfunction "1_1") (pintype "passive"))
      (node (ref "R2105") (pin "2") (pinfunction "2_2") (pintype "passive"))
    )
    (net (code "35") (name "Net-(U2100A-FB3)") (class "Default")
      (node (ref "R2104") (pin "2") (pinfunction "2_2") (pintype "passive"))
      (node (ref "R2106") (pin "1") (pinfunction "1_1") (pintype "passive"))
      (node (ref "U2100") (pin "27") (pinfunction "FB3_27") (pintype "passive"))
    )
    (net (code "36") (name "Net-(U2100B-FB5)") (class "Default")
      (node (ref "R2107") (pin "1") (pinfunction "1_1") (pintype "passive"))
      (node (ref "R2108") (pin "1") (pinfunction "1_1") (pintype "passive"))
      (node (ref "U2100") (pin "59") (pinfunction "FB5_59") (pintype "passive"))
    )
    (net (code "37") (name "Net-(U2100C-VDC)") (class "Default")
      (node (ref "C2152") (pin "1") (pinfunction "1_1") (pintype "passive"))
      (node (ref "R2109") (pin "2") (pinfunction "2_2") (pintype "passive"))
      (node (ref "R2111") (pin "1") (pinfunction "1_1") (pintype "passive"))
      (node (ref "U2100") (pin "61") (pinfunction "VDC_61") (pintype "passive"))
    )
    (net (code "38") (name "Net-(U2100C-XIN)") (class "Default")
      (node (ref "C2144") (pin "1") (pinfunction "1_1") (pintype "passive"))
      (node (ref "U2100") (pin "50") (pinfunction "XIN_50") (pintype "passive"))
      (node (ref "Y2100") (pin "2") (pinfunction "2_2") (pintype "passive"))
    )
    (net (code "39") (name "Net-(U2100C-XOUT)") (class "Default")
      (node (ref "C2148") (pin "1") (pinfunction "1_1") (pintype "passive"))
      (node (ref "U2100") (pin "51") (pinfunction "XOUT_51") (pintype "passive"))
      (node (ref "Y2100") (pin "1") (pinfunction "1_1") (pintype "passive"))
    )
    (net (code "40") (name "Net-(U2100D-CPn)") (class "Default")
      (node (ref "C2141") (pin "2") (pinfunction "2_2") (pintype "passive"))
      (node (ref "U2100") (pin "36") (pinfunction "CPn_36") (pintype "passive"))
    )
    (net (code "41") (name "Net-(U2100D-CPp)") (class "Default")
      (node (ref "C2141") (pin "1") (pinfunction "1_1") (pintype "passive"))
      (node (ref "U2100") (pin "37") (pinfunction "CPp_37") (pintype "passive"))
    )
    (net (code "42") (name "Net-(U2100D-MIC1n)") (class "Default")
      (node (ref "C2153") (pin "2") (pinfunction "2_2") (pintype "passive"))
      (node (ref "C2157") (pin "1") (pinfunction "1_1") (pintype "passive"))
      (node (ref "U2100") (pin "42") (pinfunction "MIC1n_42") (pintype "passive"))
    )
    (net (code "43") (name "Net-(U2100D-MIC1p)") (class "Default")
      (node (ref "C2151") (pin "2") (pinfunction "2_2") (pintype "passive"))
      (node (ref "C2156") (pin "1") (pinfunction "1_1") (pintype "passive"))
      (node (ref "U2100") (pin "43") (pinfunction "MIC1p_43") (pintype "passive"))
    )
    (net (code "44") (name "Net-(U2100D-SPK_OUTn)") (class "Default")
      (node (ref "FB2101") (pin "1") (pinfunction "1_1") (pintype "passive"))
      (node (ref "U2100") (pin "34") (pinfunction "SPK_OUTn_34") (pintype "passive"))
    )
    (net (code "45") (name "Net-(U2100D-SPK_OUTp)") (class "Default")
      (node (ref "FB2102") (pin "1") (pinfunction "1_1") (pintype "passive"))
      (node (ref "U2100") (pin "32") (pinfunction "SPK_OUTp_32") (pintype "passive"))
    )
    (net (code "46") (name "Net-(U2100D-VCC_SPK_HP)") (class "Default")
      (node (ref "C2138") (pin "1") (pinfunction "1_1") (pintype "passive"))
      (node (ref "FB2100") (pin "2") (pinfunction "2_2") (pintype "passive"))
      (node (ref "U2100") (pin "33") (pinfunction "VCC_SPK_HP_33") (pintype "passive"))
    )
    (net (code "47") (name "VCC-5V-RK") (class "Default")
      (node (ref "FB2100") (pin "1") (pinfunction "1_1") (pintype "passive"))
    )
    (net (code "48") (name "VCC-5V-SYS") (class "Default")
      (node (ref "R2109") (pin "1") (pinfunction "1_1") (pintype "passive"))
    )
    (net (code "49") (name "VCC3V3_PMU") (class "Default")
      (node (ref "C2116") (pin "1") (pinfunction "1_1") (pintype "passive"))
      (node (ref "R2112") (pin "1") (pinfunction "1_1") (pintype "passive"))
      (node (ref "U2100") (pin "31") (pinfunction "LDO6_400mA_31") (pintype "passive"))
    )
    (net (code "50") (name "VCC3V3_SD") (class "Default")
      (node (ref "C2124") (pin "1") (pinfunction "1_1") (pintype "passive"))
      (node (ref "U2100") (pin "58") (pinfunction "2.1A_SWOUT2_58") (pintype "passive"))
    )
    (net (code "51") (name "VCC3V3_SYS") (class "Default")
      (node (ref "C2100") (pin "1") (pinfunction "1_1") (pintype "passive"))
      (node (ref "C2102") (pin "1") (pinfunction "1_1") (pintype "passive"))
      (node (ref "C2106") (pin "1") (pinfunction "1_1") (pintype "passive"))
      (node (ref "C2108") (pin "1") (pinfunction "1_1") (pintype "passive"))
      (node (ref "C2120") (pin "1") (pinfunction "1_1") (pintype "passive"))
      (node (ref "C2122") (pin "1") (pinfunction "1_1") (pintype "passive"))
      (node (ref "C2131") (pin "1") (pinfunction "1_1") (pintype "passive"))
      (node (ref "C2134") (pin "1") (pinfunction "1_1") (pintype "passive"))
      (node (ref "C2140") (pin "1") (pinfunction "1_1") (pintype "passive"))
      (node (ref "U2100") (pin "10") (pinfunction "VCC2_10") (pintype "passive"))
      (node (ref "U2100") (pin "11") (pinfunction "VCC1_11") (pintype "passive"))
      (node (ref "U2100") (pin "22") (pinfunction "VCC5_22") (pintype "passive"))
      (node (ref "U2100") (pin "24") (pinfunction "VCC3_24") (pintype "passive"))
      (node (ref "U2100") (pin "30") (pinfunction "VCC6_30") (pintype "passive"))
      (node (ref "U2100") (pin "4") (pinfunction "VCC7_4") (pintype "passive"))
      (node (ref "U2100") (pin "45") (pinfunction "VCC_RTC_45") (pintype "passive"))
      (node (ref "U2100") (pin "54") (pinfunction "VCC9_54") (pintype "passive"))
      (node (ref "U2100") (pin "57") (pinfunction "VCC8_57") (pintype "passive"))
      (node (ref "U2100") (pin "66") (pinfunction "VCC4_66") (pintype "passive"))
    )
    (net (code "52") (name "VCCA1V8_PMU") (class "Default")
      (node (ref "C2121") (pin "1") (pinfunction "1_1") (pintype "passive"))
      (node (ref "U2100") (pin "5") (pinfunction "LDO8_400mA_5") (pintype "passive"))
    )
    (net (code "53") (name "VCCA_1V8") (class "Default")
      (node (ref "C2119") (pin "1") (pinfunction "1_1") (pintype "passive"))
      (node (ref "U2100") (pin "3") (pinfunction "LDO7_400mA_3") (pintype "passive"))
    )
    (net (code "54") (name "VCCIO_ACODEC") (class "Default")
      (node (ref "C2105") (pin "1") (pinfunction "1_1") (pintype "passive"))
      (node (ref "U2100") (pin "28") (pinfunction "LDO4_400mA_28") (pintype "passive"))
    )
    (net (code "55") (name "VCCIO_SD") (class "Default")
      (node (ref "C2109") (pin "1") (pinfunction "1_1") (pintype "passive"))
      (node (ref "U2100") (pin "29") (pinfunction "LDO5_400mA_29") (pintype "passive"))
    )
    (net (code "56") (name "VCCIO_WL") (class "Default")
      (node (ref "R2110") (pin "1") (pinfunction "1_1") (pintype "passive"))
    )
    (net (code "57") (name "VCC_1V8") (class "Default")
      (node (ref "C2135") (pin "1") (pinfunction "1_1") (pintype "passive"))
      (node (ref "C2136") (pin "1") (pinfunction "1_1") (pintype "passive"))
      (node (ref "C2137") (pin "1") (pinfunction "1_1") (pintype "passive"))
      (node (ref "L2104") (pin "1") (pinfunction "1_1") (pintype "passive"))
      (node (ref "R2107") (pin "2") (pinfunction "2_2") (pintype "passive"))
    )
    (net (code "58") (name "VCC_3V3") (class "Default")
      (node (ref "C2132") (pin "1") (pinfunction "1_1") (pintype "passive"))
      (node (ref "U2100") (pin "55") (pinfunction "2.1A_SWOUT1_55") (pintype "passive"))
    )
    (net (code "59") (name "VCC_DDR") (class "Default")
      (node (ref "C2129") (pin "1") (pinfunction "1_1") (pintype "passive"))
      (node (ref "C2130") (pin "1") (pinfunction "1_1") (pintype "passive"))
      (node (ref "L2103") (pin "1") (pinfunction "1_1") (pintype "passive"))
      (node (ref "R2104") (pin "1") (pinfunction "1_1") (pintype "passive"))
      (node (ref "U2100") (pin "26") (pinfunction "VBUCK3_26") (pintype "passive"))
    )
    (net (code "60") (name "VCC_RSV1") (class "Default")
      (node (ref "C2101") (pin "1") (pinfunction "1_1") (pintype "passive"))
      (node (ref "U2100") (pin "23") (pinfunction "LDO1_400mA_23") (pintype "passive"))
    )
    (net (code "61") (name "VCC_RSV2") (class "Default")
      (node (ref "C2123") (pin "1") (pinfunction "1_1") (pintype "passive"))
      (node (ref "U2100") (pin "6") (pinfunction "LDO9_400mA_6") (pintype "passive"))
    )
    (net (code "62") (name "VDDA0V9_PMU") (class "Default")
      (node (ref "C2104") (pin "1") (pinfunction "1_1") (pintype "passive"))
      (node (ref "U2100") (pin "20") (pinfunction "LDO3_100mA_20") (pintype "passive"))
    )
    (net (code "63") (name "VDDA_0V9") (class "Default")
      (node (ref "C2103") (pin "1") (pinfunction "1_1") (pintype "passive"))
      (node (ref "U2100") (pin "21") (pinfunction "LDO2_400mA_21") (pintype "passive"))
    )
    (net (code "64") (name "VDD_CPU") (class "Default")
      (node (ref "C2125") (pin "1") (pinfunction "1_1") (pintype "passive"))
      (node (ref "C2126") (pin "1") (pinfunction "1_1") (pintype "passive"))
      (node (ref "C2126") (pin "2") (pinfunction "2_2") (pintype "passive"))
      (node (ref "C2127") (pin "1") (pinfunction "1_1") (pintype "passive"))
      (node (ref "C2128") (pin "1") (pinfunction "1_1") (pintype "passive"))
      (node (ref "L2102") (pin "2") (pinfunction "2_2") (pintype "passive"))
      (node (ref "R2103") (pin "1") (pinfunction "1_1") (pintype "passive"))
      (node (ref "R2103") (pin "2") (pinfunction "2_2") (pintype "passive"))
      (node (ref "U2100") (pin "8") (pinfunction "FB2_8") (pintype "passive"))
    )
    (net (code "65") (name "VDD_GPU") (class "Default")
      (node (ref "C2114") (pin "1") (pinfunction "1_1") (pintype "passive"))
      (node (ref "C2115") (pin "1") (pinfunction "1_1") (pintype "passive"))
      (node (ref "C2117") (pin "1") (pinfunction "1_1") (pintype "passive"))
      (node (ref "C2117") (pin "2") (pinfunction "2_2") (pintype "passive"))
      (node (ref "C2118") (pin "1") (pinfunction "1_1") (pintype "passive"))
      (node (ref "L2101") (pin "1") (pinfunction "1_1") (pintype "passive"))
      (node (ref "R2102") (pin "1") (pinfunction "1_1") (pintype "passive"))
      (node (ref "R2102") (pin "2") (pinfunction "2_2") (pintype "passive"))
      (node (ref "U2100") (pin "64") (pinfunction "FB4_64") (pintype "passive"))
    )
    (net (code "66") (name "VDD_LOGIC") (class "Default")
      (node (ref "C2110") (pin "1") (pinfunction "1_1") (pintype "passive"))
      (node (ref "C2111") (pin "1") (pinfunction "1_1") (pintype "passive"))
      (node (ref "C2111") (pin "2") (pinfunction "2_2") (pintype "passive"))
      (node (ref "C2112") (pin "1") (pinfunction "1_1") (pintype "passive"))
      (node (ref "C2113") (pin "1") (pinfunction "1_1") (pintype "passive"))
      (node (ref "L2100") (pin "2") (pinfunction "2_2") (pintype "passive"))
      (node (ref "R2101") (pin "1") (pinfunction "1_1") (pintype "passive"))
      (node (ref "R2101") (pin "2") (pinfunction "2_2") (pintype "passive"))
      (node (ref "U2100") (pin "13") (pinfunction "FB1_13") (pintype "passive"))
    )
  )
)
